# ps_for_AOM_AZ.net
KiCad netlist of a schematic drawn in EAGLE
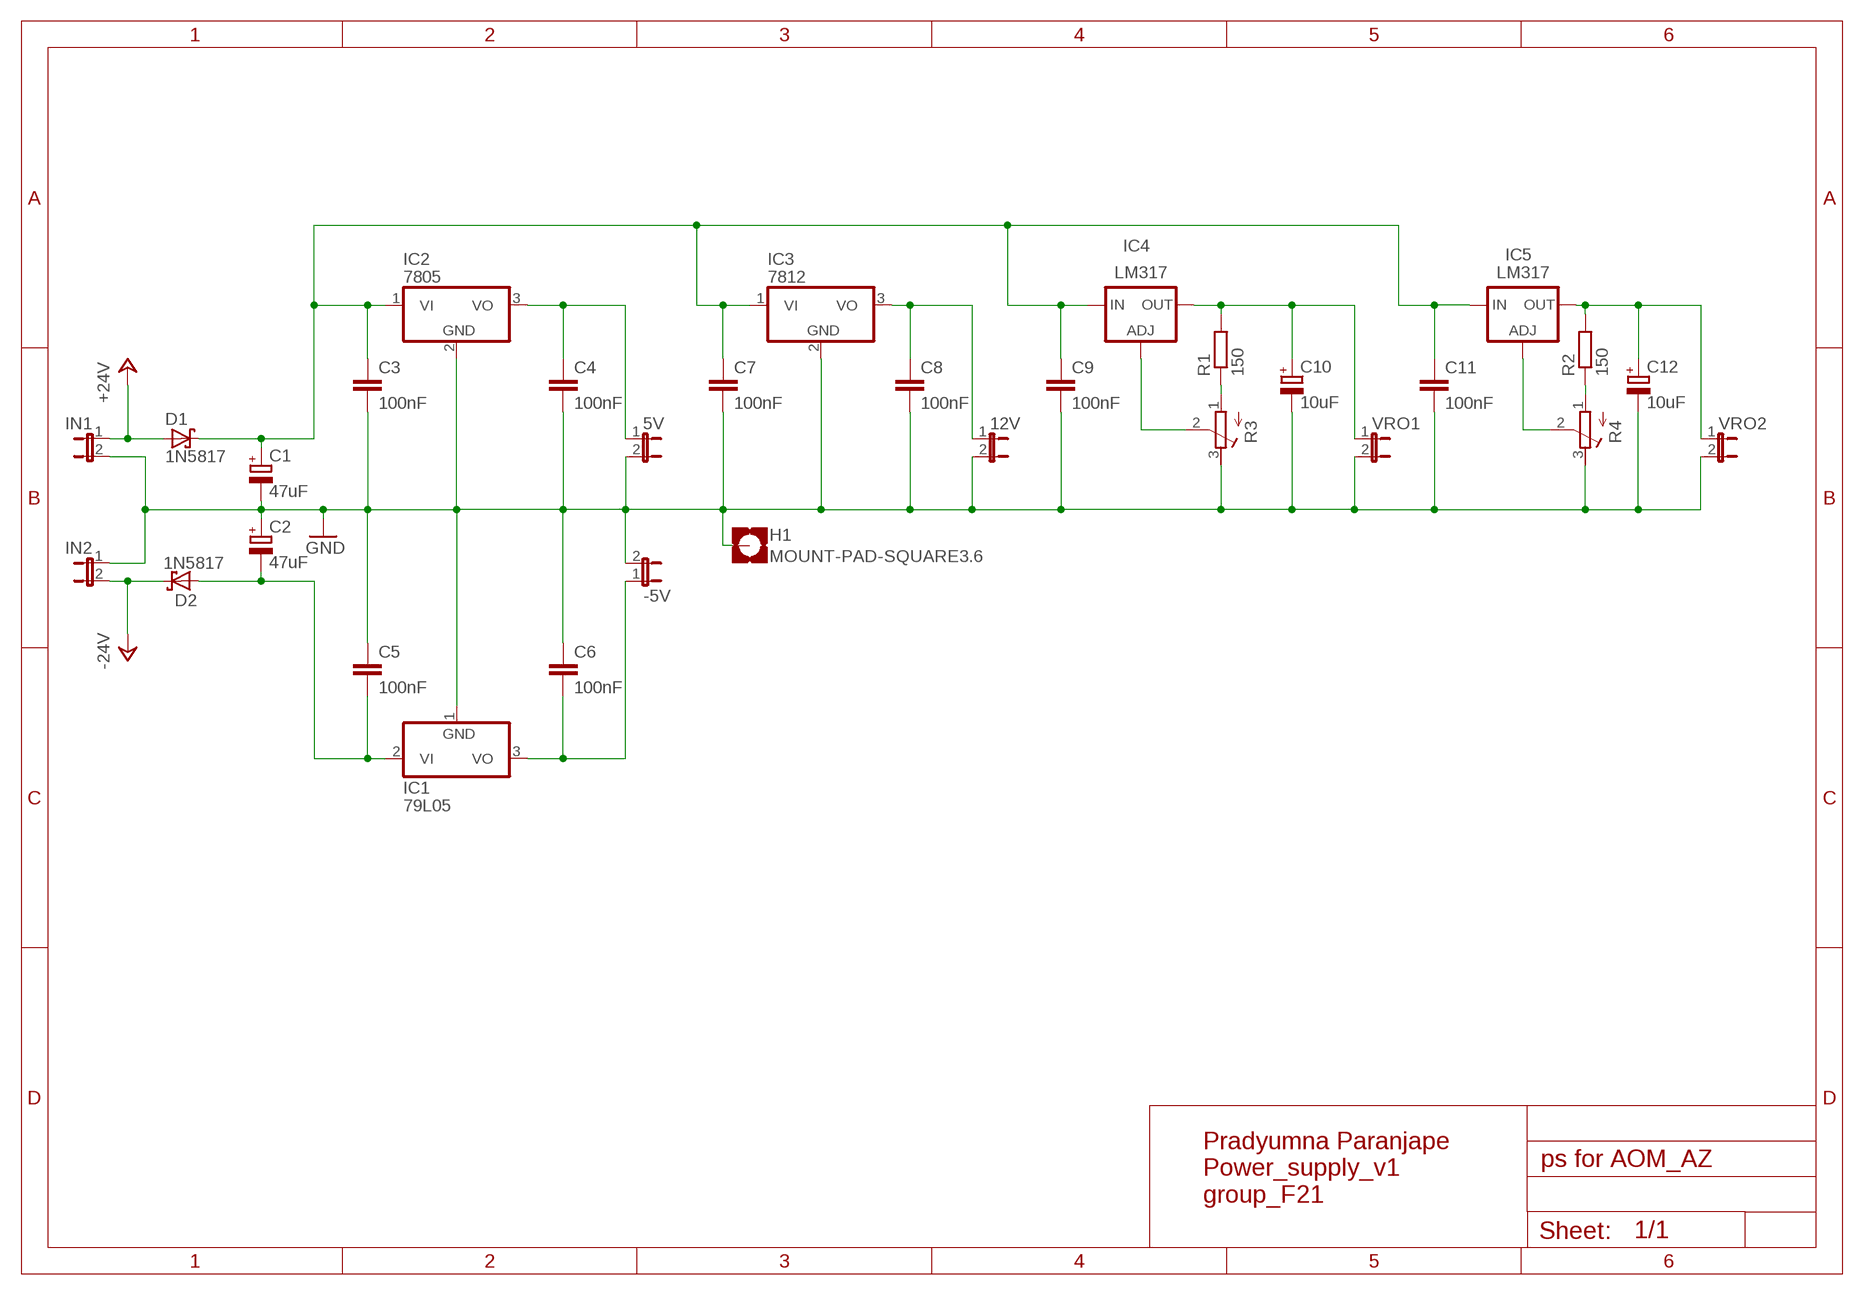
[diagram p0: schematic, sheet 1]

(export (version "E")
  (design (tool "Eeschema 10.0.6"))
  (components
    (comp (ref "-5V")
      (value "JP1E")
      (footprint "eagle-import:JP1")
      (libsource (lib "eagle-import") (part "JP1E"))
    )
    (comp (ref "5V")
      (value "JP1E")
      (footprint "eagle-import:JP1")
      (libsource (lib "eagle-import") (part "JP1E"))
    )
    (comp (ref "12V")
      (value "JP1E")
      (footprint "eagle-import:JP1")
      (libsource (lib "eagle-import") (part "JP1E"))
    )
    (comp (ref "C1")
      (value "47uF")
      (footprint "eagle-import:E5-6")
      (libsource (lib "eagle-import") (part "CPOL-EUE5-6"))
    )
    (comp (ref "C2")
      (value "47uF")
      (footprint "eagle-import:E5-6")
      (libsource (lib "eagle-import") (part "CPOL-EUE5-6"))
    )
    (comp (ref "C3")
      (value "100nF")
      (footprint "eagle-import:C1206K")
      (libsource (lib "eagle-import") (part "C-EUC1206K"))
    )
    (comp (ref "C4")
      (value "100nF")
      (footprint "eagle-import:C1206K")
      (libsource (lib "eagle-import") (part "C-EUC1206K"))
    )
    (comp (ref "C5")
      (value "100nF")
      (footprint "eagle-import:C1206K")
      (libsource (lib "eagle-import") (part "C-EUC1206K"))
    )
    (comp (ref "C6")
      (value "100nF")
      (footprint "eagle-import:C1206K")
      (libsource (lib "eagle-import") (part "C-EUC1206K"))
    )
    (comp (ref "C7")
      (value "100nF")
      (footprint "eagle-import:C1206K")
      (libsource (lib "eagle-import") (part "C-EUC1206K"))
    )
    (comp (ref "C8")
      (value "100nF")
      (footprint "eagle-import:C1206K")
      (libsource (lib "eagle-import") (part "C-EUC1206K"))
    )
    (comp (ref "C9")
      (value "100nF")
      (footprint "eagle-import:C1206K")
      (libsource (lib "eagle-import") (part "C-EUC1206K"))
    )
    (comp (ref "C10")
      (value "10uF")
      (footprint "eagle-import:E1,8-4")
      (libsource (lib "eagle-import") (part "CPOL-EUE1.8-4"))
    )
    (comp (ref "C11")
      (value "100nF")
      (footprint "eagle-import:C1206K")
      (libsource (lib "eagle-import") (part "C-EUC1206K"))
    )
    (comp (ref "C12")
      (value "10uF")
      (footprint "eagle-import:E1,8-4")
      (libsource (lib "eagle-import") (part "CPOL-EUE1.8-4"))
    )
    (comp (ref "D1")
      (value "1N5817")
      (footprint "eagle-import:DO41-7.6")
      (libsource (lib "eagle-import") (part "1N5817-B"))
    )
    (comp (ref "D2")
      (value "1N5817")
      (footprint "eagle-import:DO41-7.6")
      (libsource (lib "eagle-import") (part "1N5817-B"))
    )
    (comp (ref "H1")
      (value "MOUNT-PAD-SQUARE3.6")
      (footprint "eagle-import:3,6-PAD-SQUARE")
      (libsource (lib "eagle-import") (part "MOUNT-PAD-SQUARE3.6"))
    )
    (comp (ref "IC1")
      (value "79L05")
      (footprint "eagle-import:TO92")
      (libsource (lib "eagle-import") (part "79L05"))
    )
    (comp (ref "IC2")
      (value "7805")
      (footprint "eagle-import:TO220H")
      (libsource (lib "eagle-import") (part "78T05"))
    )
    (comp (ref "IC3")
      (value "7812")
      (footprint "eagle-import:TO220H")
      (libsource (lib "eagle-import") (part "78T12"))
    )
    (comp (ref "IC4")
      (value "LM317")
      (footprint "eagle-import:TO220H")
      (libsource (lib "eagle-import") (part "LM317?TO220H"))
    )
    (comp (ref "IC5")
      (value "LM317")
      (footprint "eagle-import:TO220H")
      (libsource (lib "eagle-import") (part "LM317?TO220H"))
    )
    (comp (ref "IN1")
      (value "JP1E")
      (footprint "eagle-import:JP1")
      (libsource (lib "eagle-import") (part "JP1E"))
    )
    (comp (ref "IN2")
      (value "JP1E")
      (footprint "eagle-import:JP1")
      (libsource (lib "eagle-import") (part "JP1E"))
    )
    (comp (ref "R1")
      (value "150")
      (footprint "eagle-import:R1206")
      (libsource (lib "eagle-import") (part "R-EU_R1206"))
    )
    (comp (ref "R2")
      (value "150")
      (footprint "eagle-import:R1206")
      (libsource (lib "eagle-import") (part "R-EU_R1206"))
    )
    (comp (ref "R3")
      (value "R-TRIMM3296Y")
      (footprint "eagle-import:RTRIM3296Y")
      (libsource (lib "eagle-import") (part "R-TRIMM3296Y"))
    )
    (comp (ref "R4")
      (value "R-TRIMM3296Y")
      (footprint "eagle-import:RTRIM3296Y")
      (libsource (lib "eagle-import") (part "R-TRIMM3296Y"))
    )
    (comp (ref "VRO1")
      (value "JP1E")
      (footprint "eagle-import:JP1")
      (libsource (lib "eagle-import") (part "JP1E"))
    )
    (comp (ref "VRO2")
      (value "JP1E")
      (footprint "eagle-import:JP1")
      (libsource (lib "eagle-import") (part "JP1E"))
    )
  )
  (nets
    (net (code "1") (name "+24V") (class "Default")
      (node (ref "D1") (pin "A") (pinfunction "A_A") (pintype "passive"))
      (node (ref "IN1") (pin "1") (pinfunction "1_1") (pintype "passive"))
    )
    (net (code "2") (name "-24V") (class "Default")
      (node (ref "D2") (pin "C") (pinfunction "C_C") (pintype "passive"))
      (node (ref "IN2") (pin "2") (pinfunction "2_2") (pintype "passive"))
    )
    (net (code "3") (name "GND") (class "Default")
      (node (ref "-5V") (pin "2") (pinfunction "2_2") (pintype "passive"))
      (node (ref "12V") (pin "2") (pinfunction "2_2") (pintype "passive"))
      (node (ref "5V") (pin "2") (pinfunction "2_2") (pintype "passive"))
      (node (ref "C1") (pin "-") (pinfunction "-_-") (pintype "passive"))
      (node (ref "C10") (pin "-") (pinfunction "-_-") (pintype "passive"))
      (node (ref "C11") (pin "2") (pinfunction "2_2") (pintype "passive"))
      (node (ref "C12") (pin "-") (pinfunction "-_-") (pintype "passive"))
      (node (ref "C2") (pin "+") (pinfunction "+_+") (pintype "passive"))
      (node (ref "C3") (pin "2") (pinfunction "2_2") (pintype "passive"))
      (node (ref "C4") (pin "2") (pinfunction "2_2") (pintype "passive"))
      (node (ref "C5") (pin "1") (pinfunction "1_1") (pintype "passive"))
      (node (ref "C6") (pin "1") (pinfunction "1_1") (pintype "passive"))
      (node (ref "C7") (pin "2") (pinfunction "2_2") (pintype "passive"))
      (node (ref "C8") (pin "2") (pinfunction "2_2") (pintype "passive"))
      (node (ref "C9") (pin "2") (pinfunction "2_2") (pintype "passive"))
      (node (ref "H1") (pin "B3,6") (pinfunction "MOUNT_B3,6") (pintype "passive"))
      (node (ref "IC1") (pin "1") (pinfunction "GND_1") (pintype "passive"))
      (node (ref "IC2") (pin "2") (pinfunction "GND_2") (pintype "passive"))
      (node (ref "IC3") (pin "2") (pinfunction "GND_2") (pintype "passive"))
      (node (ref "IN1") (pin "2") (pinfunction "2_2") (pintype "passive"))
      (node (ref "IN2") (pin "1") (pinfunction "1_1") (pintype "passive"))
      (node (ref "R3") (pin "3") (pinfunction "E_3") (pintype "passive"))
      (node (ref "R4") (pin "3") (pinfunction "E_3") (pintype "passive"))
      (node (ref "VRO1") (pin "2") (pinfunction "2_2") (pintype "passive"))
      (node (ref "VRO2") (pin "2") (pinfunction "2_2") (pintype "passive"))
    )
    (net (code "4") (name "Net-(IC1-VI)") (class "Default")
      (node (ref "C2") (pin "-") (pinfunction "-_-") (pintype "passive"))
      (node (ref "C5") (pin "2") (pinfunction "2_2") (pintype "passive"))
      (node (ref "D2") (pin "A") (pinfunction "A_A") (pintype "passive"))
      (node (ref "IC1") (pin "2") (pinfunction "VI_2") (pintype "input"))
    )
    (net (code "5") (name "Net-(IC1-VO)") (class "Default")
      (node (ref "-5V") (pin "1") (pinfunction "1_1") (pintype "passive"))
      (node (ref "C6") (pin "2") (pinfunction "2_2") (pintype "passive"))
      (node (ref "IC1") (pin "3") (pinfunction "VO_3") (pintype "passive"))
    )
    (net (code "6") (name "Net-(IC2-VI)") (class "Default")
      (node (ref "C1") (pin "+") (pinfunction "+_+") (pintype "passive"))
      (node (ref "C11") (pin "1") (pinfunction "1_1") (pintype "passive"))
      (node (ref "C3") (pin "1") (pinfunction "1_1") (pintype "passive"))
      (node (ref "C7") (pin "1") (pinfunction "1_1") (pintype "passive"))
      (node (ref "C9") (pin "1") (pinfunction "1_1") (pintype "passive"))
      (node (ref "D1") (pin "C") (pinfunction "C_C") (pintype "passive"))
      (node (ref "IC2") (pin "1") (pinfunction "VI_1") (pintype "input"))
      (node (ref "IC3") (pin "1") (pinfunction "VI_1") (pintype "input"))
      (node (ref "IC4") (pin "3") (pinfunction "IN_3") (pintype "input"))
      (node (ref "IC5") (pin "3") (pinfunction "IN_3") (pintype "input"))
    )
    (net (code "7") (name "Net-(IC2-VO)") (class "Default")
      (node (ref "5V") (pin "1") (pinfunction "1_1") (pintype "passive"))
      (node (ref "C4") (pin "1") (pinfunction "1_1") (pintype "passive"))
      (node (ref "IC2") (pin "3") (pinfunction "VO_3") (pintype "passive"))
    )
    (net (code "8") (name "Net-(IC3-VO)") (class "Default")
      (node (ref "12V") (pin "1") (pinfunction "1_1") (pintype "passive"))
      (node (ref "C8") (pin "1") (pinfunction "1_1") (pintype "passive"))
      (node (ref "IC3") (pin "3") (pinfunction "VO_3") (pintype "passive"))
    )
    (net (code "9") (name "Net-(IC4-ADJ)") (class "Default")
      (node (ref "IC4") (pin "1") (pinfunction "ADJ_1") (pintype "input"))
      (node (ref "R3") (pin "2") (pinfunction "S_2") (pintype "passive"))
    )
    (net (code "10") (name "Net-(IC4-OUT)") (class "Default")
      (node (ref "C10") (pin "+") (pinfunction "+_+") (pintype "passive"))
      (node (ref "IC4") (pin "2") (pinfunction "OUT_2") (pintype "passive"))
      (node (ref "R1") (pin "2") (pinfunction "2_2") (pintype "passive"))
      (node (ref "VRO1") (pin "1") (pinfunction "1_1") (pintype "passive"))
    )
    (net (code "11") (name "Net-(IC5-ADJ)") (class "Default")
      (node (ref "IC5") (pin "1") (pinfunction "ADJ_1") (pintype "input"))
      (node (ref "R4") (pin "2") (pinfunction "S_2") (pintype "passive"))
    )
    (net (code "12") (name "Net-(IC5-OUT)") (class "Default")
      (node (ref "C12") (pin "+") (pinfunction "+_+") (pintype "passive"))
      (node (ref "IC5") (pin "2") (pinfunction "OUT_2") (pintype "passive"))
      (node (ref "R2") (pin "2") (pinfunction "2_2") (pintype "passive"))
      (node (ref "VRO2") (pin "1") (pinfunction "1_1") (pintype "passive"))
    )
    (net (code "13") (name "Net-(R3-A)") (class "Default")
      (node (ref "R1") (pin "1") (pinfunction "1_1") (pintype "passive"))
      (node (ref "R3") (pin "1") (pinfunction "A_1") (pintype "passive"))
    )
    (net (code "14") (name "Net-(R4-A)") (class "Default")
      (node (ref "R2") (pin "1") (pinfunction "1_1") (pintype "passive"))
      (node (ref "R4") (pin "1") (pinfunction "A_1") (pintype "passive"))
    )
  )
)
